# Motor-Driver-Sheet.net
KiCad netlist of a schematic drawn in Altium Designer
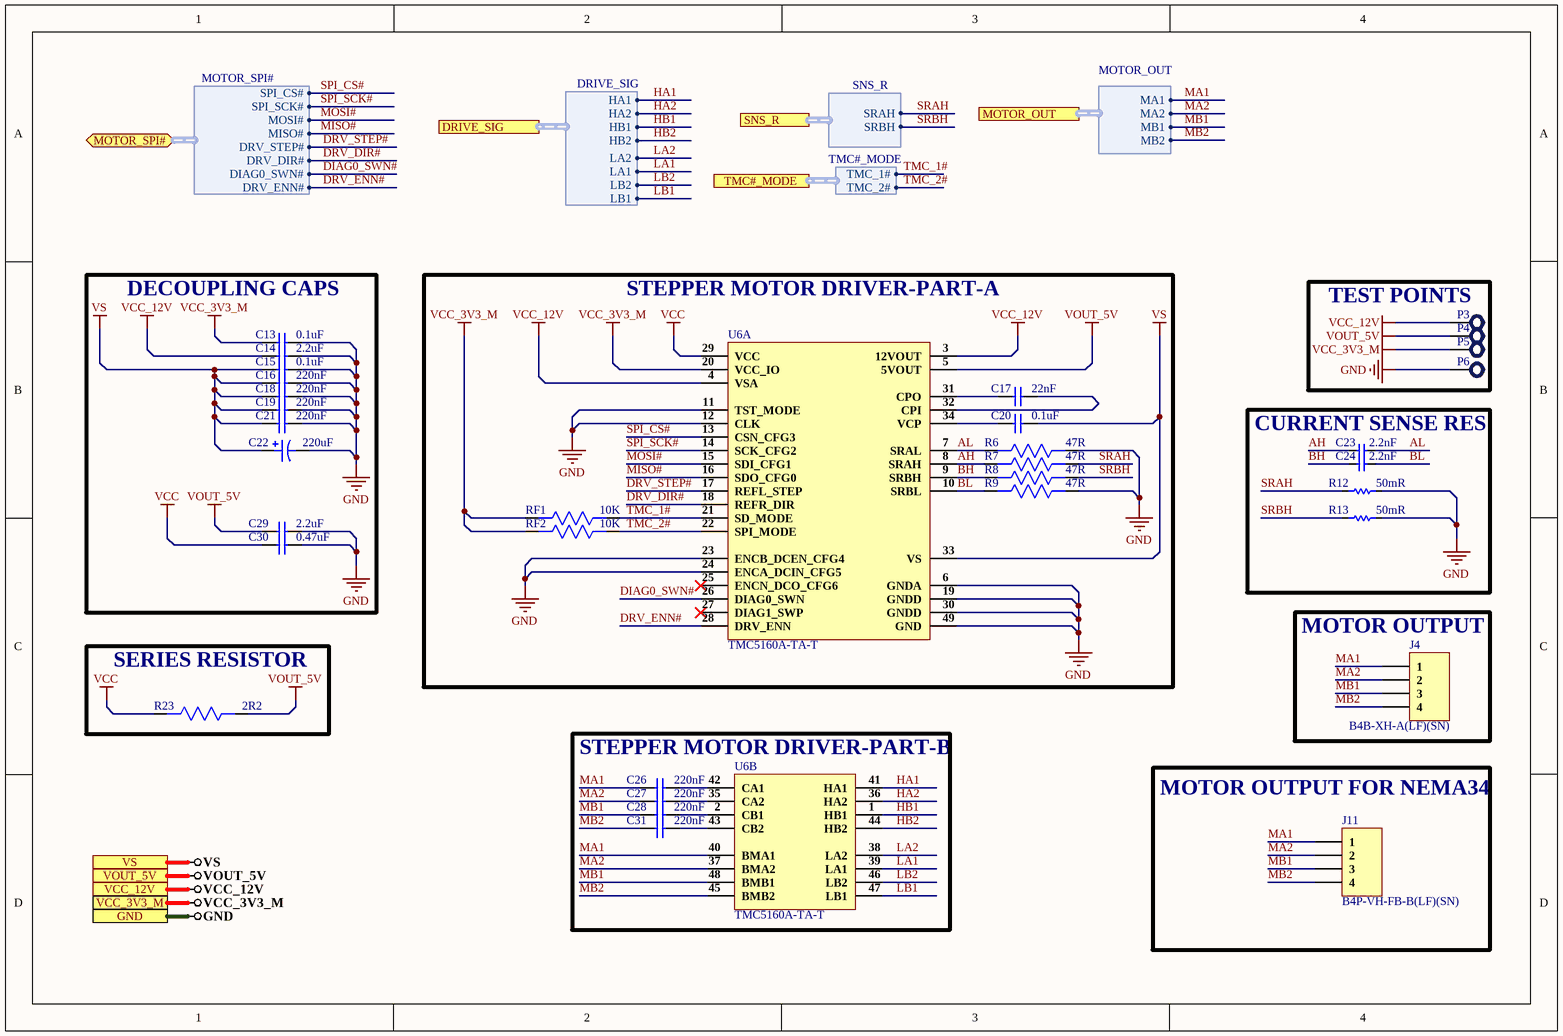
[diagram p0: Motor-Driver-Sheet.SchDoc]

(export (version "E")
  (design (tool "Eeschema 10.0.6"))
  (components
    (comp (ref "C13")
      (value "0.1uF")
      (footprint "Cap 0603")
      (description "Cap Ceramic 0.1uF 50VDC X7R 10% SMD 0603 Paper T/R")
      (fields
        (field (name "MANUFACTURER") "Samsung")
        (field (name "MANUFACTURER PART NUMBER") "CL10B104KB8NNNC")
      )
      (libsource (lib "Cole_Benson") (part "CL10B104KB8NNNC"))
    )
    (comp (ref "C14")
      (value "2.2uF")
      (footprint "Cap 0603")
      (description "CAP, 2.2µF, 35V, 10%, X5R, 0603")
      (fields
        (field (name "MANUFACTURER") "Murata")
        (field (name "MANUFACTURER PART NUMBER") "GRM188R6YA225KA12D")
      )
      (libsource (lib "Cole_Benson") (part "GRM188R6YA225KA12D"))
    )
    (comp (ref "C15")
      (value "0.1uF")
      (footprint "Cap 0603")
      (description "Cap Ceramic 0.1uF 50VDC X7R 10% SMD 0603 Paper T/R")
      (fields
        (field (name "MANUFACTURER") "Samsung")
        (field (name "MANUFACTURER PART NUMBER") "CL10B104KB8NNNC")
      )
      (libsource (lib "Cole_Benson") (part "CL10B104KB8NNNC"))
    )
    (comp (ref "C16")
      (value "220nF")
      (footprint "Cap0805")
      (description "Cap Ceramic 0.22uF 100V X7R 10% SMD 0805 125°C Embossed T/R")
      (fields
        (field (name "MANUFACTURER") "Kyocera AVX")
        (field (name "MANUFACTURER PART NUMBER") "08051C224K4T2A")
      )
      (libsource (lib "Cole_Benson") (part "08051C224K4T2A"))
    )
    (comp (ref "C17")
      (value "22nF")
      (footprint "Cap 0603")
      (description "0603 .022uF 100volts X7R 10% T=0.8mm")
      (fields
        (field (name "MANUFACTURER") "TDK")
        (field (name "MANUFACTURER PART NUMBER") "CGA3E2X7R2A223K080AA")
      )
      (libsource (lib "Cole_Benson") (part "CGA3E2X7R2A223K080AA"))
    )
    (comp (ref "C18")
      (value "220nF")
      (footprint "Cap0805")
      (description "Cap Ceramic 0.22uF 100V X7R 10% SMD 0805 125°C Embossed T/R")
      (fields
        (field (name "MANUFACTURER") "Kyocera AVX")
        (field (name "MANUFACTURER PART NUMBER") "08051C224K4T2A")
      )
      (libsource (lib "Cole_Benson") (part "08051C224K4T2A"))
    )
    (comp (ref "C19")
      (value "220nF")
      (footprint "Cap0805")
      (description "Cap Ceramic 0.22uF 100V X7R 10% SMD 0805 125°C Embossed T/R")
      (fields
        (field (name "MANUFACTURER") "Kyocera AVX")
        (field (name "MANUFACTURER PART NUMBER") "08051C224K4T2A")
      )
      (libsource (lib "Cole_Benson") (part "08051C224K4T2A"))
    )
    (comp (ref "C20")
      (value "0.1uF")
      (footprint "Cap 0603")
      (description "Cap Ceramic 0.1uF 50VDC X7R 10% SMD 0603 Paper T/R")
      (fields
        (field (name "MANUFACTURER") "Samsung")
        (field (name "MANUFACTURER PART NUMBER") "CL10B104KB8NNNC")
      )
      (libsource (lib "Cole_Benson") (part "CL10B104KB8NNNC"))
    )
    (comp (ref "C21")
      (value "220nF")
      (footprint "Cap0805")
      (description "Cap Ceramic 0.22uF 100V X7R 10% SMD 0805 125°C Embossed T/R")
      (fields
        (field (name "MANUFACTURER") "Kyocera AVX")
        (field (name "MANUFACTURER PART NUMBER") "08051C224K4T2A")
      )
      (libsource (lib "Cole_Benson") (part "08051C224K4T2A"))
    )
    (comp (ref "C22")
      (value "220uF")
      (footprint "189RV0038")
      (description "220uF 63V 225mA@100KHz ±20% SMD,D10xL10.5mm Aluminum Electrolytic Capacitors - SMD ROHS")
      (fields (field (name "MANUFACTURER") "KNSCHA") (field (name "MANUFACTURER PART NUMBER") "189RV0038"))
      (libsource (lib "Cole_Benson") (part "189RV0038"))
    )
    (comp (ref "C23")
      (value "2.2nF")
      (footprint "Cap-0603")
      (description "CAP CER 2200PF 50V X7R 0603")
      (fields
        (field (name "MANUFACTURER") "Yageo")
        (field (name "MANUFACTURER PART NUMBER") "CC0603KRX7R9BB222")
      )
      (libsource (lib "eSpark_centralized_Library(2022)") (part "CC0603KRX7R9BB222"))
    )
    (comp (ref "C24")
      (value "2.2nF")
      (footprint "Cap-0603")
      (description "CAP CER 2200PF 50V X7R 0603")
      (fields
        (field (name "MANUFACTURER") "Yageo")
        (field (name "MANUFACTURER PART NUMBER") "CC0603KRX7R9BB222")
      )
      (libsource (lib "eSpark_centralized_Library(2022)") (part "CC0603KRX7R9BB222"))
    )
    (comp (ref "C26")
      (value "220nF")
      (footprint "Cap0805")
      (description "CAP CER 0.22UF 100V X7R 0805")
      (fields
        (field (name "MANUFACTURER") "Kyocera AVX")
        (field (name "MANUFACTURER PART NUMBER") "08051C224K4T2A")
      )
      (libsource (lib "Cole_Benson") (part "08051C224K4T2A"))
    )
    (comp (ref "C27")
      (value "220nF")
      (footprint "Cap0805")
      (description "CAP CER 0.22UF 100V X7R 0805")
      (fields
        (field (name "MANUFACTURER") "Kyocera AVX")
        (field (name "MANUFACTURER PART NUMBER") "08051C224K4T2A")
      )
      (libsource (lib "Cole_Benson") (part "08051C224K4T2A"))
    )
    (comp (ref "C28")
      (value "220nF")
      (footprint "Cap0805")
      (description "CAP CER 0.22UF 100V X7R 0805")
      (fields
        (field (name "MANUFACTURER") "Kyocera AVX")
        (field (name "MANUFACTURER PART NUMBER") "08051C224K4T2A")
      )
      (libsource (lib "Cole_Benson") (part "08051C224K4T2A"))
    )
    (comp (ref "C29")
      (value "2.2uF")
      (footprint "Cap 0603")
      (description "CAP, 2.2µF, 35V, 10%, X5R, 0603")
      (fields
        (field (name "MANUFACTURER") "Murata")
        (field (name "MANUFACTURER PART NUMBER") "GRM188R6YA225KA12D")
      )
      (libsource (lib "Cole_Benson") (part "GRM188R6YA225KA12D"))
    )
    (comp (ref "C30")
      (value "0.47uF")
      (footprint "Cap 0603")
      (description "CAP CER 0.47uF 50V X7R 0603")
      (fields
        (field (name "MANUFACTURER") "Taiyo Yuden")
        (field (name "MANUFACTURER PART NUMBER") "UMK107B7474KA-TR")
      )
      (libsource (lib "Cole_Benson") (part "UMK107B7474KA-TR"))
    )
    (comp (ref "C31")
      (value "220nF")
      (footprint "Cap0805")
      (description "CAP CER 0.22UF 100V X7R 0805")
      (fields
        (field (name "MANUFACTURER") "Kyocera AVX")
        (field (name "MANUFACTURER PART NUMBER") "08051C224K4T2A")
      )
      (libsource (lib "Cole_Benson") (part "08051C224K4T2A"))
    )
    (comp (ref "J4")
      (value "B4B-XH-A(LF)(SN)")
      (footprint "B4B-XH-A(LF)(SN)")
      (description "CONN HEADER VERT 4POS 2.5MM")
      (fields (field (name "MANUFACTURER") "JST"))
      (libsource (lib "Cole_Benson") (part "B4B-XH-A(LF)(SN)"))
    )
    (comp (ref "J11")
      (value "B4P-VH-FB-B(LF)(SN)")
      (footprint "B4P-VH-FB-B(LF)(SN)")
      (description "CONN HEADER VERT 4POS 3.96MM")
      (fields (field (name "MANUFACTURER") "JST"))
      (libsource (lib "Cole_Benson") (part "B4P-VH-FB-B(LF)(SN)"))
    )
    (comp (ref "P3")
      (value "Test Point")
      (footprint "TEST POINT")
      (description "Test Point ON")
      (libsource (lib "Cole_Benson") (part "TEST POINT"))
    )
    (comp (ref "P4")
      (value "Test Point")
      (footprint "TEST POINT")
      (description "Test Point ON")
      (libsource (lib "Cole_Benson") (part "TEST POINT"))
    )
    (comp (ref "P5")
      (value "Test Point")
      (footprint "TEST POINT")
      (description "Test Point ON")
      (libsource (lib "Cole_Benson") (part "TEST POINT"))
    )
    (comp (ref "P6")
      (value "Test Point")
      (footprint "TEST POINT")
      (description "Test Point ON")
      (libsource (lib "Cole_Benson") (part "TEST POINT"))
    )
    (comp (ref "R6")
      (value "47R")
      (footprint "Res0603")
      (description "RES SMD 47OHM 0.1W 0603")
      (fields
        (field (name "MANUFACTURER") "Yageo")
        (field (name "MANUFACTURER PART NUMBER") "RC0603FR-0747RL")
      )
      (libsource (lib "Cole_Benson") (part "RC0603FR-0747RL"))
    )
    (comp (ref "R7")
      (value "47R")
      (footprint "Res0603")
      (description "RES SMD 47OHM 0.1W 0603")
      (fields
        (field (name "MANUFACTURER") "Yageo")
        (field (name "MANUFACTURER PART NUMBER") "RC0603FR-0747RL")
      )
      (libsource (lib "Cole_Benson") (part "RC0603FR-0747RL"))
    )
    (comp (ref "R8")
      (value "47R")
      (footprint "Res0603")
      (description "RES SMD 47OHM 0.1W 0603")
      (fields
        (field (name "MANUFACTURER") "Yageo")
        (field (name "MANUFACTURER PART NUMBER") "RC0603FR-0747RL")
      )
      (libsource (lib "Cole_Benson") (part "RC0603FR-0747RL"))
    )
    (comp (ref "R9")
      (value "47R")
      (footprint "Res0603")
      (description "RES SMD 47OHM 0.1W 0603")
      (fields
        (field (name "MANUFACTURER") "Yageo")
        (field (name "MANUFACTURER PART NUMBER") "RC0603FR-0747RL")
      )
      (libsource (lib "Cole_Benson") (part "RC0603FR-0747RL"))
    )
    (comp (ref "R12")
      (value "50mR")
      (footprint "RES-2512")
      (description "2W 50mΩ ±1% 2512 Current Sense Resistors/Shunt Resistors ROHS")
      (fields
        (field (name "MANUFACTURER") "Ever Ohms Tech")
        (field (name "MANUFACTURER PART NUMBER") "CRH2512FR050E04Z")
      )
      (libsource (lib "eSpark_centralized_Library(2022)") (part "CRH2512FR050E04Z"))
    )
    (comp (ref "R13")
      (value "50mR")
      (footprint "RES-2512")
      (description "2W 50mΩ ±1% 2512 Current Sense Resistors/Shunt Resistors ROHS")
      (fields
        (field (name "MANUFACTURER") "Ever Ohms Tech")
        (field (name "MANUFACTURER PART NUMBER") "CRH2512FR050E04Z")
      )
      (libsource (lib "eSpark_centralized_Library(2022)") (part "CRH2512FR050E04Z"))
    )
    (comp (ref "R23")
      (value "2R2")
      (footprint "Res0603")
      (description "RES SMD 2.2OHM 0603")
      (fields
        (field (name "MANUFACTURER") "Panasonic")
        (field (name "MANUFACTURER PART NUMBER") "ERJ-3GEYJ2R2V")
      )
      (libsource (lib "Cole_Benson") (part "ERJ3GEYJ2R2V"))
    )
    (comp (ref "RF1")
      (value "10K")
      (footprint "Res0603")
      (description "RES SMD 10K Ohm 1% 1/10W 0603")
      (fields
        (field (name "MANUFACTURER") "Yageo")
        (field (name "MANUFACTURER PART NUMBER") "RC0603FR-0710KL")
      )
      (libsource (lib "Cole_Benson") (part "RC0603FR-0710KL"))
    )
    (comp (ref "RF2")
      (value "10K")
      (footprint "Res0603")
      (description "RES SMD 10K Ohm 1% 1/10W 0603")
      (fields
        (field (name "MANUFACTURER") "Yageo")
        (field (name "MANUFACTURER PART NUMBER") "RC0603FR-0710KL")
      )
      (libsource (lib "Cole_Benson") (part "RC0603FR-0710KL"))
    )
    (comp (ref "U6")
      (value "TMC5160A-TA-T")
      (footprint "48-tqfp-ep (7x7)")
      (description "IC MTR DRVR BIPOLAR 8-60V 48TQFP")
      (fields (field (name "MANUFACTURER") "Trinamic"))
      (libsource (lib "Cole_Benson") (part "TMC5160A-TA-T"))
    )
  )
  (nets
    (net (code "6") (name "/AH") (class "Default")
      (node (ref "C23") (pin "1") (pinfunction "1_1") (pintype "passive"))
      (node (ref "R7") (pin "2") (pintype "passive"))
      (node (ref "U6") (pin "8") (pinfunction "SRAH_8") (pintype "passive"))
    )
    (net (code "7") (name "/AL") (class "Default")
      (node (ref "C23") (pin "2") (pinfunction "2_2") (pintype "passive"))
      (node (ref "R6") (pin "2") (pintype "passive"))
      (node (ref "U6") (pin "7") (pinfunction "SRAL_7") (pintype "passive"))
    )
    (net (code "8") (name "/BH") (class "Default")
      (node (ref "C24") (pin "1") (pinfunction "1_1") (pintype "passive"))
      (node (ref "R8") (pin "2") (pintype "passive"))
      (node (ref "U6") (pin "9") (pinfunction "SRBH_9") (pintype "passive"))
    )
    (net (code "9") (name "/BL") (class "Default")
      (node (ref "C24") (pin "2") (pinfunction "2_2") (pintype "passive"))
      (node (ref "R9") (pin "2") (pintype "passive"))
      (node (ref "U6") (pin "10") (pinfunction "SRBL_10") (pintype "passive"))
    )
    (net (code "10") (name "/DIAG0_SWN#") (class "Default")
      (node (ref "U6") (pin "26") (pinfunction "DIAG0_SWN_26") (pintype "passive"))
    )
    (net (code "11") (name "/DRV_DIR#") (class "Default")
      (node (ref "U6") (pin "18") (pinfunction "REFR_DIR_18") (pintype "passive"))
    )
    (net (code "12") (name "/DRV_ENN#") (class "Default")
      (node (ref "U6") (pin "28") (pinfunction "DRV_ENN_28") (pintype "passive"))
    )
    (net (code "13") (name "/DRV_STEP#") (class "Default")
      (node (ref "U6") (pin "17") (pinfunction "REFL_STEP_17") (pintype "passive"))
    )
    (net (code "14") (name "/HA1") (class "Default")
      (node (ref "U6") (pin "41") (pinfunction "HA1_41") (pintype "passive"))
    )
    (net (code "15") (name "/HA2") (class "Default")
      (node (ref "U6") (pin "36") (pinfunction "HA2_36") (pintype "passive"))
    )
    (net (code "16") (name "/HB1") (class "Default")
      (node (ref "U6") (pin "1") (pinfunction "HB1_1") (pintype "passive"))
    )
    (net (code "17") (name "/HB2") (class "Default")
      (node (ref "U6") (pin "44") (pinfunction "HB2_44") (pintype "passive"))
    )
    (net (code "18") (name "/LA1") (class "Default")
      (node (ref "U6") (pin "39") (pinfunction "LA1_39") (pintype "passive"))
    )
    (net (code "19") (name "/LA2") (class "Default")
      (node (ref "U6") (pin "38") (pinfunction "LA2_38") (pintype "passive"))
    )
    (net (code "20") (name "/LB1") (class "Default")
      (node (ref "U6") (pin "47") (pinfunction "LB1_47") (pintype "passive"))
    )
    (net (code "21") (name "/LB2") (class "Default")
      (node (ref "U6") (pin "46") (pinfunction "LB2_46") (pintype "passive"))
    )
    (net (code "22") (name "/MA1") (class "Default")
      (node (ref "C26") (pin "1") (pinfunction "1_1") (pintype "passive"))
      (node (ref "J11") (pin "1") (pinfunction "1_1") (pintype "passive"))
      (node (ref "J4") (pin "1") (pinfunction "1_1") (pintype "passive"))
      (node (ref "U6") (pin "40") (pinfunction "BMA1_40") (pintype "passive"))
    )
    (net (code "23") (name "/MA2") (class "Default")
      (node (ref "C27") (pin "1") (pinfunction "1_1") (pintype "passive"))
      (node (ref "J11") (pin "2") (pinfunction "2_2") (pintype "passive"))
      (node (ref "J4") (pin "2") (pinfunction "2_2") (pintype "passive"))
      (node (ref "U6") (pin "37") (pinfunction "BMA2_37") (pintype "passive"))
    )
    (net (code "24") (name "/MB1") (class "Default")
      (node (ref "C28") (pin "1") (pinfunction "1_1") (pintype "passive"))
      (node (ref "J11") (pin "3") (pinfunction "3_3") (pintype "passive"))
      (node (ref "J4") (pin "3") (pinfunction "3_3") (pintype "passive"))
      (node (ref "U6") (pin "48") (pinfunction "BMB1_48") (pintype "passive"))
    )
    (net (code "25") (name "/MB2") (class "Default")
      (node (ref "C31") (pin "1") (pinfunction "1_1") (pintype "passive"))
      (node (ref "J11") (pin "4") (pinfunction "4_4") (pintype "passive"))
      (node (ref "J4") (pin "4") (pinfunction "4_4") (pintype "passive"))
      (node (ref "U6") (pin "45") (pinfunction "BMB2_45") (pintype "passive"))
    )
    (net (code "26") (name "/MISO#") (class "Default")
      (node (ref "U6") (pin "16") (pinfunction "SDO_CFG0_16") (pintype "passive"))
    )
    (net (code "27") (name "/MOSI#") (class "Default")
      (node (ref "U6") (pin "15") (pinfunction "SDI_CFG1_15") (pintype "passive"))
    )
    (net (code "28") (name "/SPI_CS#") (class "Default")
      (node (ref "U6") (pin "13") (pinfunction "CSN_CFG3_13") (pintype "passive"))
    )
    (net (code "29") (name "/SPI_SCK#") (class "Default")
      (node (ref "U6") (pin "14") (pinfunction "SCK_CFG2_14") (pintype "passive"))
    )
    (net (code "30") (name "/SRAH") (class "Default")
      (node (ref "R12") (pin "1") (pinfunction "1_1") (pintype "passive"))
      (node (ref "R7") (pin "1") (pintype "passive"))
    )
    (net (code "31") (name "/SRBH") (class "Default")
      (node (ref "R13") (pin "1") (pinfunction "1_1") (pintype "passive"))
      (node (ref "R8") (pin "1") (pintype "passive"))
    )
    (net (code "32") (name "/TMC_1#") (class "Default")
      (node (ref "RF1") (pin "1") (pintype "passive"))
      (node (ref "U6") (pin "21") (pinfunction "SD_MODE_21") (pintype "passive"))
    )
    (net (code "33") (name "/TMC_2#") (class "Default")
      (node (ref "RF2") (pin "1") (pintype "passive"))
      (node (ref "U6") (pin "22") (pinfunction "SPI_MODE_22") (pintype "passive"))
    )
    (net (code "39") (name "GND") (class "Default")
      (node (ref "C13") (pin "2") (pinfunction "2_2") (pintype "passive"))
      (node (ref "C14") (pin "2") (pinfunction "2_2") (pintype "passive"))
      (node (ref "C15") (pin "2") (pinfunction "2_2") (pintype "passive"))
      (node (ref "C16") (pin "2") (pinfunction "2_2") (pintype "passive"))
      (node (ref "C18") (pin "2") (pinfunction "2_2") (pintype "passive"))
      (node (ref "C19") (pin "2") (pinfunction "2_2") (pintype "passive"))
      (node (ref "C21") (pin "2") (pinfunction "2_2") (pintype "passive"))
      (node (ref "C22") (pin "2") (pinfunction "2_2") (pintype "passive"))
      (node (ref "C29") (pin "2") (pinfunction "2_2") (pintype "passive"))
      (node (ref "C30") (pin "2") (pinfunction "2_2") (pintype "passive"))
      (node (ref "P6") (pin "1") (pinfunction "1_1") (pintype "passive"))
      (node (ref "R12") (pin "2") (pinfunction "2_2") (pintype "passive"))
      (node (ref "R13") (pin "2") (pinfunction "2_2") (pintype "passive"))
      (node (ref "R6") (pin "1") (pintype "passive"))
      (node (ref "R9") (pin "1") (pintype "passive"))
      (node (ref "U6") (pin "11") (pinfunction "TST_MODE_11") (pintype "passive"))
      (node (ref "U6") (pin "12") (pinfunction "CLK_12") (pintype "passive"))
      (node (ref "U6") (pin "19") (pinfunction "GNDD_19") (pintype "passive"))
      (node (ref "U6") (pin "23") (pinfunction "ENCB_DCEN_CFG4_23") (pintype "passive"))
      (node (ref "U6") (pin "24") (pinfunction "ENCA_DCIN_CFG5_24") (pintype "passive"))
      (node (ref "U6") (pin "30") (pinfunction "GNDD_30") (pintype "passive"))
      (node (ref "U6") (pin "49") (pinfunction "GND_49") (pintype "passive"))
      (node (ref "U6") (pin "6") (pinfunction "GNDA_6") (pintype "passive"))
    )
    (net (code "40") (name "Net-(U6A-CPI)") (class "Default")
      (node (ref "C17") (pin "2") (pinfunction "2_2") (pintype "passive"))
      (node (ref "U6") (pin "32") (pinfunction "CPI_32") (pintype "passive"))
    )
    (net (code "41") (name "Net-(U6A-CPO)") (class "Default")
      (node (ref "C17") (pin "1") (pinfunction "1_1") (pintype "passive"))
      (node (ref "U6") (pin "31") (pinfunction "CPO_31") (pintype "passive"))
    )
    (net (code "42") (name "Net-(U6A-VCP)") (class "Default")
      (node (ref "C20") (pin "1") (pinfunction "1_1") (pintype "passive"))
      (node (ref "U6") (pin "34") (pinfunction "VCP_34") (pintype "passive"))
    )
    (net (code "43") (name "Net-(U6B-CA1)") (class "Default")
      (node (ref "C26") (pin "2") (pinfunction "2_2") (pintype "passive"))
      (node (ref "U6") (pin "42") (pinfunction "CA1_42") (pintype "passive"))
    )
    (net (code "44") (name "Net-(U6B-CA2)") (class "Default")
      (node (ref "C27") (pin "2") (pinfunction "2_2") (pintype "passive"))
      (node (ref "U6") (pin "35") (pinfunction "CA2_35") (pintype "passive"))
    )
    (net (code "45") (name "Net-(U6B-CB1)") (class "Default")
      (node (ref "C28") (pin "2") (pinfunction "2_2") (pintype "passive"))
      (node (ref "U6") (pin "2") (pinfunction "CB1_2") (pintype "passive"))
    )
    (net (code "46") (name "Net-(U6B-CB2)") (class "Default")
      (node (ref "C31") (pin "2") (pinfunction "2_2") (pintype "passive"))
      (node (ref "U6") (pin "43") (pinfunction "CB2_43") (pintype "passive"))
    )
    (net (code "47") (name "VCC") (class "Default")
      (node (ref "C30") (pin "1") (pinfunction "1_1") (pintype "passive"))
      (node (ref "R23") (pin "2") (pintype "passive"))
      (node (ref "U6") (pin "29") (pinfunction "VCC_29") (pintype "passive"))
    )
    (net (code "48") (name "VCC_3V3_M") (class "Default")
      (node (ref "C13") (pin "1") (pinfunction "1_1") (pintype "passive"))
      (node (ref "P5") (pin "1") (pinfunction "1_1") (pintype "passive"))
      (node (ref "RF1") (pin "2") (pintype "passive"))
      (node (ref "RF2") (pin "2") (pintype "passive"))
      (node (ref "U6") (pin "20") (pinfunction "VCC_IO_20") (pintype "passive"))
    )
    (net (code "49") (name "VCC_12V") (class "Default")
      (node (ref "C14") (pin "1") (pinfunction "1_1") (pintype "passive"))
      (node (ref "P3") (pin "1") (pinfunction "1_1") (pintype "passive"))
      (node (ref "U6") (pin "3") (pinfunction "12VOUT_3") (pintype "passive"))
      (node (ref "U6") (pin "4") (pinfunction "VSA_4") (pintype "passive"))
    )
    (net (code "50") (name "VOUT_5V") (class "Default")
      (node (ref "C29") (pin "1") (pinfunction "1_1") (pintype "passive"))
      (node (ref "P4") (pin "1") (pinfunction "1_1") (pintype "passive"))
      (node (ref "R23") (pin "1") (pintype "passive"))
      (node (ref "U6") (pin "5") (pinfunction "5VOUT_5") (pintype "passive"))
    )
    (net (code "51") (name "VS") (class "Default")
      (node (ref "C15") (pin "1") (pinfunction "1_1") (pintype "passive"))
      (node (ref "C16") (pin "1") (pinfunction "1_1") (pintype "passive"))
      (node (ref "C18") (pin "1") (pinfunction "1_1") (pintype "passive"))
      (node (ref "C19") (pin "1") (pinfunction "1_1") (pintype "passive"))
      (node (ref "C20") (pin "2") (pinfunction "2_2") (pintype "passive"))
      (node (ref "C21") (pin "1") (pinfunction "1_1") (pintype "passive"))
      (node (ref "C22") (pin "1") (pinfunction "1_1") (pintype "passive"))
      (node (ref "U6") (pin "33") (pinfunction "VS_33") (pintype "passive"))
    )
    (net (code "52") (name "unconnected-(U6A-DIAG1_SWP-Pad27)") (class "Default")
      (node (ref "U6") (pin "27") (pinfunction "DIAG1_SWP_27") (pintype "passive+no_connect"))
    )
    (net (code "53") (name "unconnected-(U6A-ENCN_DCO_CFG6-Pad25)") (class "Default")
      (node (ref "U6") (pin "25") (pinfunction "ENCN_DCO_CFG6_25") (pintype "passive+no_connect"))
    )
  )
)
